# 12_OUT.net
KiCad netlist of a schematic drawn in Altium Designer
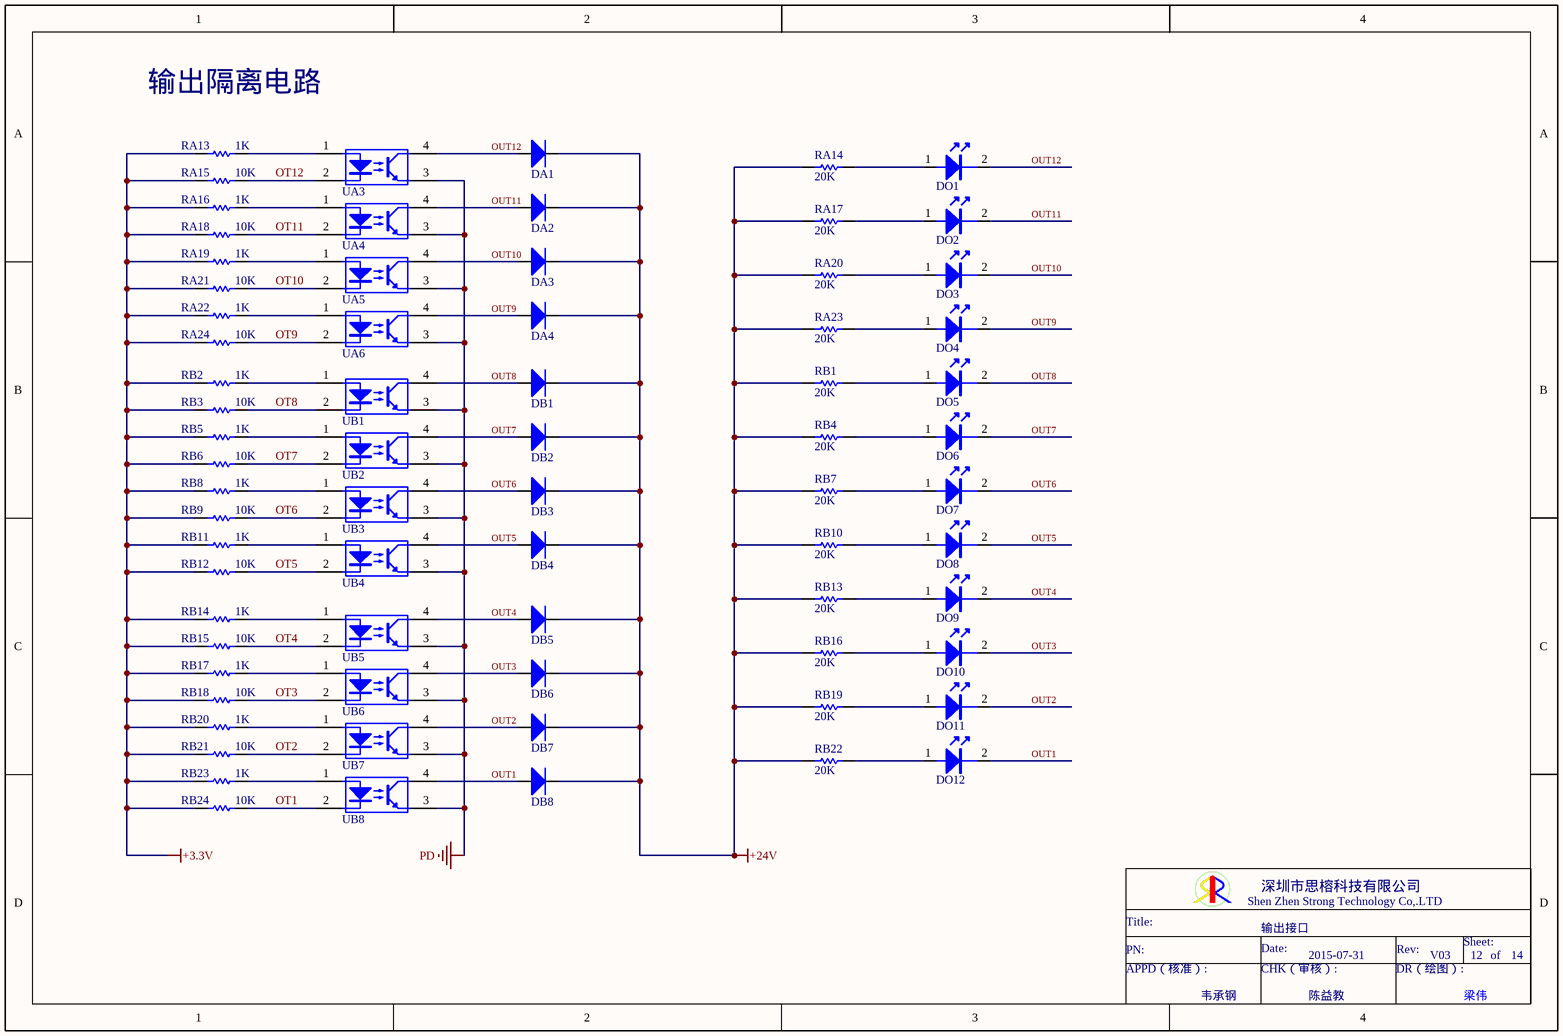
[diagram p0: 12_OUT.SchDoc]

(export (version "E")
  (design (tool "Eeschema 10.0.6"))
  (components
    (comp (ref "DA1")
      (value "IN4148W T4")
      (footprint "1206D")
      (description "二极管")
      (libsource (lib "Mylibrary") (part "D"))
    )
    (comp (ref "DA2")
      (value "IN4148W T4")
      (footprint "1206D")
      (description "二极管")
      (libsource (lib "Mylibrary") (part "D"))
    )
    (comp (ref "DA3")
      (value "IN4148W T4")
      (footprint "1206D")
      (description "二极管")
      (libsource (lib "Mylibrary") (part "D"))
    )
    (comp (ref "DA4")
      (value "IN4148W T4")
      (footprint "1206D")
      (description "二极管")
      (libsource (lib "Mylibrary") (part "D"))
    )
    (comp (ref "DB1")
      (value "IN4148W T4")
      (footprint "1206D")
      (description "二极管")
      (libsource (lib "Mylibrary") (part "D"))
    )
    (comp (ref "DB2")
      (value "IN4148W T4")
      (footprint "1206D")
      (description "二极管")
      (libsource (lib "Mylibrary") (part "D"))
    )
    (comp (ref "DB3")
      (value "IN4148W T4")
      (footprint "1206D")
      (description "二极管")
      (libsource (lib "Mylibrary") (part "D"))
    )
    (comp (ref "DB4")
      (value "IN4148W T4")
      (footprint "1206D")
      (description "二极管")
      (libsource (lib "Mylibrary") (part "D"))
    )
    (comp (ref "DB5")
      (value "IN4148W T4")
      (footprint "1206D")
      (description "二极管")
      (libsource (lib "Mylibrary") (part "D"))
    )
    (comp (ref "DB6")
      (value "IN4148W T4")
      (footprint "1206D")
      (description "二极管")
      (libsource (lib "Mylibrary") (part "D"))
    )
    (comp (ref "DB7")
      (value "IN4148W T4")
      (footprint "1206D")
      (description "二极管")
      (libsource (lib "Mylibrary") (part "D"))
    )
    (comp (ref "DB8")
      (value "IN4148W T4")
      (footprint "1206D")
      (description "二极管")
      (libsource (lib "Mylibrary") (part "D"))
    )
    (comp (ref "DO1")
      (value "LED灯 白发红光")
      (footprint "D0603")
      (description "LED灯")
      (libsource (lib "Mylibrary") (part "LED"))
    )
    (comp (ref "DO2")
      (value "LED灯 白发红光")
      (footprint "D0603")
      (description "LED灯")
      (libsource (lib "Mylibrary") (part "LED"))
    )
    (comp (ref "DO3")
      (value "LED灯 白发红光")
      (footprint "D0603")
      (description "LED灯")
      (libsource (lib "Mylibrary") (part "LED"))
    )
    (comp (ref "DO4")
      (value "LED灯 白发红光")
      (footprint "D0603")
      (description "LED灯")
      (libsource (lib "Mylibrary") (part "LED"))
    )
    (comp (ref "DO5")
      (value "LED灯 白发红光")
      (footprint "D0603")
      (description "LED灯")
      (libsource (lib "Mylibrary") (part "LED"))
    )
    (comp (ref "DO6")
      (value "LED灯 白发红光")
      (footprint "D0603")
      (description "LED灯")
      (libsource (lib "Mylibrary") (part "LED"))
    )
    (comp (ref "DO7")
      (value "LED灯 白发红光")
      (footprint "D0603")
      (description "LED灯")
      (libsource (lib "Mylibrary") (part "LED"))
    )
    (comp (ref "DO8")
      (value "LED灯 白发红光")
      (footprint "D0603")
      (description "LED灯")
      (libsource (lib "Mylibrary") (part "LED"))
    )
    (comp (ref "DO9")
      (value "LED灯 白发红光")
      (footprint "D0603")
      (description "LED灯")
      (libsource (lib "Mylibrary") (part "LED"))
    )
    (comp (ref "DO10")
      (value "LED灯 白发红光")
      (footprint "D0603")
      (description "LED灯")
      (libsource (lib "Mylibrary") (part "LED"))
    )
    (comp (ref "DO11")
      (value "LED灯 白发红光")
      (footprint "D0603")
      (description "LED灯")
      (libsource (lib "Mylibrary") (part "LED"))
    )
    (comp (ref "DO12")
      (value "LED灯 白发红光")
      (footprint "D0603")
      (description "LED灯")
      (libsource (lib "Mylibrary") (part "LED"))
    )
    (comp (ref "RA13") (value "1K") (footprint "0603R") (libsource (lib "Mylibrary") (part "RES")))
    (comp (ref "RA14") (value "20K") (footprint "0603R") (libsource (lib "Mylibrary") (part "RES")))
    (comp (ref "RA15") (value "10K") (footprint "0603R") (libsource (lib "Mylibrary") (part "RES")))
    (comp (ref "RA16") (value "1K") (footprint "0603R") (libsource (lib "Mylibrary") (part "RES")))
    (comp (ref "RA17") (value "20K") (footprint "0603R") (libsource (lib "Mylibrary") (part "RES")))
    (comp (ref "RA18") (value "10K") (footprint "0603R") (libsource (lib "Mylibrary") (part "RES")))
    (comp (ref "RA19") (value "1K") (footprint "0603R") (libsource (lib "Mylibrary") (part "RES")))
    (comp (ref "RA20") (value "20K") (footprint "0603R") (libsource (lib "Mylibrary") (part "RES")))
    (comp (ref "RA21") (value "10K") (footprint "0603R") (libsource (lib "Mylibrary") (part "RES")))
    (comp (ref "RA22") (value "1K") (footprint "0603R") (libsource (lib "Mylibrary") (part "RES")))
    (comp (ref "RA23") (value "20K") (footprint "0603R") (libsource (lib "Mylibrary") (part "RES")))
    (comp (ref "RA24") (value "10K") (footprint "0603R") (libsource (lib "Mylibrary") (part "RES")))
    (comp (ref "RB1") (value "20K") (footprint "0603R") (libsource (lib "Mylibrary") (part "RES")))
    (comp (ref "RB2") (value "1K") (footprint "0603R") (libsource (lib "Mylibrary") (part "RES")))
    (comp (ref "RB3") (value "10K") (footprint "0603R") (libsource (lib "Mylibrary") (part "RES")))
    (comp (ref "RB4") (value "20K") (footprint "0603R") (libsource (lib "Mylibrary") (part "RES")))
    (comp (ref "RB5") (value "1K") (footprint "0603R") (libsource (lib "Mylibrary") (part "RES")))
    (comp (ref "RB6") (value "10K") (footprint "0603R") (libsource (lib "Mylibrary") (part "RES")))
    (comp (ref "RB7") (value "20K") (footprint "0603R") (libsource (lib "Mylibrary") (part "RES")))
    (comp (ref "RB8") (value "1K") (footprint "0603R") (libsource (lib "Mylibrary") (part "RES")))
    (comp (ref "RB9") (value "10K") (footprint "0603R") (libsource (lib "Mylibrary") (part "RES")))
    (comp (ref "RB10") (value "20K") (footprint "0603R") (libsource (lib "Mylibrary") (part "RES")))
    (comp (ref "RB11") (value "1K") (footprint "0603R") (libsource (lib "Mylibrary") (part "RES")))
    (comp (ref "RB12") (value "10K") (footprint "0603R") (libsource (lib "Mylibrary") (part "RES")))
    (comp (ref "RB13") (value "20K") (footprint "0603R") (libsource (lib "Mylibrary") (part "RES")))
    (comp (ref "RB14") (value "1K") (footprint "0603R") (libsource (lib "Mylibrary") (part "RES")))
    (comp (ref "RB15") (value "10K") (footprint "0603R") (libsource (lib "Mylibrary") (part "RES")))
    (comp (ref "RB16") (value "20K") (footprint "0603R") (libsource (lib "Mylibrary") (part "RES")))
    (comp (ref "RB17") (value "1K") (footprint "0603R") (libsource (lib "Mylibrary") (part "RES")))
    (comp (ref "RB18") (value "10K") (footprint "0603R") (libsource (lib "Mylibrary") (part "RES")))
    (comp (ref "RB19") (value "20K") (footprint "0603R") (libsource (lib "Mylibrary") (part "RES")))
    (comp (ref "RB20") (value "1K") (footprint "0603R") (libsource (lib "Mylibrary") (part "RES")))
    (comp (ref "RB21") (value "10K") (footprint "0603R") (libsource (lib "Mylibrary") (part "RES")))
    (comp (ref "RB22") (value "20K") (footprint "0603R") (libsource (lib "Mylibrary") (part "RES")))
    (comp (ref "RB23") (value "1K") (footprint "0603R") (libsource (lib "Mylibrary") (part "RES")))
    (comp (ref "RB24") (value "10K") (footprint "0603R") (libsource (lib "Mylibrary") (part "RES")))
    (comp (ref "UA3")
      (value "AQY212GS")
      (footprint "SOP4-2.54")
      (libsource (lib "Mylibrary") (part "TLP281"))
    )
    (comp (ref "UA4")
      (value "AQY212GS")
      (footprint "SOP4-2.54")
      (libsource (lib "Mylibrary") (part "TLP281"))
    )
    (comp (ref "UA5")
      (value "AQY212GS")
      (footprint "SOP4-2.54")
      (libsource (lib "Mylibrary") (part "TLP281"))
    )
    (comp (ref "UA6")
      (value "AQY212GS")
      (footprint "SOP4-2.54")
      (libsource (lib "Mylibrary") (part "TLP281"))
    )
    (comp (ref "UB1")
      (value "AQY212GS")
      (footprint "SOP4-2.54")
      (libsource (lib "Mylibrary") (part "TLP281"))
    )
    (comp (ref "UB2")
      (value "AQY212GS")
      (footprint "SOP4-2.54")
      (libsource (lib "Mylibrary") (part "TLP281"))
    )
    (comp (ref "UB3")
      (value "AQY212GS")
      (footprint "SOP4-2.54")
      (libsource (lib "Mylibrary") (part "TLP281"))
    )
    (comp (ref "UB4")
      (value "AQY212GS")
      (footprint "SOP4-2.54")
      (libsource (lib "Mylibrary") (part "TLP281"))
    )
    (comp (ref "UB5")
      (value "AQY212GS")
      (footprint "SOP4-2.54")
      (libsource (lib "Mylibrary") (part "TLP281"))
    )
    (comp (ref "UB6")
      (value "AQY212GS")
      (footprint "SOP4-2.54")
      (libsource (lib "Mylibrary") (part "TLP281"))
    )
    (comp (ref "UB7")
      (value "AQY212GS")
      (footprint "SOP4-2.54")
      (libsource (lib "Mylibrary") (part "TLP281"))
    )
    (comp (ref "UB8")
      (value "AQY212GS")
      (footprint "SOP4-2.54")
      (libsource (lib "Mylibrary") (part "TLP281"))
    )
  )
  (nets
    (net (code "1") (name "+3.3V") (class "Default")
      (node (ref "RA13") (pin "1") (pinfunction "1_1") (pintype "passive"))
      (node (ref "RA15") (pin "1") (pinfunction "1_1") (pintype "passive"))
      (node (ref "RA16") (pin "1") (pinfunction "1_1") (pintype "passive"))
      (node (ref "RA18") (pin "1") (pinfunction "1_1") (pintype "passive"))
      (node (ref "RA19") (pin "1") (pinfunction "1_1") (pintype "passive"))
      (node (ref "RA21") (pin "1") (pinfunction "1_1") (pintype "passive"))
      (node (ref "RA22") (pin "1") (pinfunction "1_1") (pintype "passive"))
      (node (ref "RA24") (pin "1") (pinfunction "1_1") (pintype "passive"))
      (node (ref "RB11") (pin "1") (pinfunction "1_1") (pintype "passive"))
      (node (ref "RB12") (pin "1") (pinfunction "1_1") (pintype "passive"))
      (node (ref "RB14") (pin "1") (pinfunction "1_1") (pintype "passive"))
      (node (ref "RB15") (pin "1") (pinfunction "1_1") (pintype "passive"))
      (node (ref "RB17") (pin "1") (pinfunction "1_1") (pintype "passive"))
      (node (ref "RB18") (pin "1") (pinfunction "1_1") (pintype "passive"))
      (node (ref "RB2") (pin "1") (pinfunction "1_1") (pintype "passive"))
      (node (ref "RB20") (pin "1") (pinfunction "1_1") (pintype "passive"))
      (node (ref "RB21") (pin "1") (pinfunction "1_1") (pintype "passive"))
      (node (ref "RB23") (pin "1") (pinfunction "1_1") (pintype "passive"))
      (node (ref "RB24") (pin "1") (pinfunction "1_1") (pintype "passive"))
      (node (ref "RB3") (pin "1") (pinfunction "1_1") (pintype "passive"))
      (node (ref "RB5") (pin "1") (pinfunction "1_1") (pintype "passive"))
      (node (ref "RB6") (pin "1") (pinfunction "1_1") (pintype "passive"))
      (node (ref "RB8") (pin "1") (pinfunction "1_1") (pintype "passive"))
      (node (ref "RB9") (pin "1") (pinfunction "1_1") (pintype "passive"))
    )
    (net (code "2") (name "+24V") (class "Default")
      (node (ref "DA1") (pin "2") (pinfunction "2_2") (pintype "passive"))
      (node (ref "DA2") (pin "2") (pinfunction "2_2") (pintype "passive"))
      (node (ref "DA3") (pin "2") (pinfunction "2_2") (pintype "passive"))
      (node (ref "DA4") (pin "2") (pinfunction "2_2") (pintype "passive"))
      (node (ref "DB1") (pin "2") (pinfunction "2_2") (pintype "passive"))
      (node (ref "DB2") (pin "2") (pinfunction "2_2") (pintype "passive"))
      (node (ref "DB3") (pin "2") (pinfunction "2_2") (pintype "passive"))
      (node (ref "DB4") (pin "2") (pinfunction "2_2") (pintype "passive"))
      (node (ref "DB5") (pin "2") (pinfunction "2_2") (pintype "passive"))
      (node (ref "DB6") (pin "2") (pinfunction "2_2") (pintype "passive"))
      (node (ref "DB7") (pin "2") (pinfunction "2_2") (pintype "passive"))
      (node (ref "DB8") (pin "2") (pinfunction "2_2") (pintype "passive"))
      (node (ref "RA14") (pin "1") (pinfunction "1_1") (pintype "passive"))
      (node (ref "RA17") (pin "1") (pinfunction "1_1") (pintype "passive"))
      (node (ref "RA20") (pin "1") (pinfunction "1_1") (pintype "passive"))
      (node (ref "RA23") (pin "1") (pinfunction "1_1") (pintype "passive"))
      (node (ref "RB1") (pin "1") (pinfunction "1_1") (pintype "passive"))
      (node (ref "RB10") (pin "1") (pinfunction "1_1") (pintype "passive"))
      (node (ref "RB13") (pin "1") (pinfunction "1_1") (pintype "passive"))
      (node (ref "RB16") (pin "1") (pinfunction "1_1") (pintype "passive"))
      (node (ref "RB19") (pin "1") (pinfunction "1_1") (pintype "passive"))
      (node (ref "RB22") (pin "1") (pinfunction "1_1") (pintype "passive"))
      (node (ref "RB4") (pin "1") (pinfunction "1_1") (pintype "passive"))
      (node (ref "RB7") (pin "1") (pinfunction "1_1") (pintype "passive"))
    )
    (net (code "3") (name "/OT1") (class "Default")
      (node (ref "RB24") (pin "2") (pinfunction "2_2") (pintype "passive"))
      (node (ref "UB8") (pin "2") (pinfunction "LED_Cathode_2") (pintype "passive"))
    )
    (net (code "4") (name "/OT2") (class "Default")
      (node (ref "RB21") (pin "2") (pinfunction "2_2") (pintype "passive"))
      (node (ref "UB7") (pin "2") (pinfunction "LED_Cathode_2") (pintype "passive"))
    )
    (net (code "5") (name "/OT3") (class "Default")
      (node (ref "RB18") (pin "2") (pinfunction "2_2") (pintype "passive"))
      (node (ref "UB6") (pin "2") (pinfunction "LED_Cathode_2") (pintype "passive"))
    )
    (net (code "6") (name "/OT4") (class "Default")
      (node (ref "RB15") (pin "2") (pinfunction "2_2") (pintype "passive"))
      (node (ref "UB5") (pin "2") (pinfunction "LED_Cathode_2") (pintype "passive"))
    )
    (net (code "7") (name "/OT5") (class "Default")
      (node (ref "RB12") (pin "2") (pinfunction "2_2") (pintype "passive"))
      (node (ref "UB4") (pin "2") (pinfunction "LED_Cathode_2") (pintype "passive"))
    )
    (net (code "8") (name "/OT6") (class "Default")
      (node (ref "RB9") (pin "2") (pinfunction "2_2") (pintype "passive"))
      (node (ref "UB3") (pin "2") (pinfunction "LED_Cathode_2") (pintype "passive"))
    )
    (net (code "9") (name "/OT7") (class "Default")
      (node (ref "RB6") (pin "2") (pinfunction "2_2") (pintype "passive"))
      (node (ref "UB2") (pin "2") (pinfunction "LED_Cathode_2") (pintype "passive"))
    )
    (net (code "10") (name "/OT8") (class "Default")
      (node (ref "RB3") (pin "2") (pinfunction "2_2") (pintype "passive"))
      (node (ref "UB1") (pin "2") (pinfunction "LED_Cathode_2") (pintype "passive"))
    )
    (net (code "11") (name "/OT9") (class "Default")
      (node (ref "RA24") (pin "2") (pinfunction "2_2") (pintype "passive"))
      (node (ref "UA6") (pin "2") (pinfunction "LED_Cathode_2") (pintype "passive"))
    )
    (net (code "12") (name "/OT10") (class "Default")
      (node (ref "RA21") (pin "2") (pinfunction "2_2") (pintype "passive"))
      (node (ref "UA5") (pin "2") (pinfunction "LED_Cathode_2") (pintype "passive"))
    )
    (net (code "13") (name "/OT11") (class "Default")
      (node (ref "RA18") (pin "2") (pinfunction "2_2") (pintype "passive"))
      (node (ref "UA4") (pin "2") (pinfunction "LED_Cathode_2") (pintype "passive"))
    )
    (net (code "14") (name "/OT12") (class "Default")
      (node (ref "RA15") (pin "2") (pinfunction "2_2") (pintype "passive"))
      (node (ref "UA3") (pin "2") (pinfunction "LED_Cathode_2") (pintype "passive"))
    )
    (net (code "15") (name "/OUT1") (class "Default")
      (node (ref "DB8") (pin "1") (pinfunction "1_1") (pintype "passive"))
      (node (ref "DO12") (pin "2") (pinfunction "2_2") (pintype "passive"))
      (node (ref "UB8") (pin "4") (pinfunction "Collector_4") (pintype "passive"))
    )
    (net (code "16") (name "/OUT2") (class "Default")
      (node (ref "DB7") (pin "1") (pinfunction "1_1") (pintype "passive"))
      (node (ref "DO11") (pin "2") (pinfunction "2_2") (pintype "passive"))
      (node (ref "UB7") (pin "4") (pinfunction "Collector_4") (pintype "passive"))
    )
    (net (code "17") (name "/OUT3") (class "Default")
      (node (ref "DB6") (pin "1") (pinfunction "1_1") (pintype "passive"))
      (node (ref "DO10") (pin "2") (pinfunction "2_2") (pintype "passive"))
      (node (ref "UB6") (pin "4") (pinfunction "Collector_4") (pintype "passive"))
    )
    (net (code "18") (name "/OUT4") (class "Default")
      (node (ref "DB5") (pin "1") (pinfunction "1_1") (pintype "passive"))
      (node (ref "DO9") (pin "2") (pinfunction "2_2") (pintype "passive"))
      (node (ref "UB5") (pin "4") (pinfunction "Collector_4") (pintype "passive"))
    )
    (net (code "19") (name "/OUT5") (class "Default")
      (node (ref "DB4") (pin "1") (pinfunction "1_1") (pintype "passive"))
      (node (ref "DO8") (pin "2") (pinfunction "2_2") (pintype "passive"))
      (node (ref "UB4") (pin "4") (pinfunction "Collector_4") (pintype "passive"))
    )
    (net (code "20") (name "/OUT6") (class "Default")
      (node (ref "DB3") (pin "1") (pinfunction "1_1") (pintype "passive"))
      (node (ref "DO7") (pin "2") (pinfunction "2_2") (pintype "passive"))
      (node (ref "UB3") (pin "4") (pinfunction "Collector_4") (pintype "passive"))
    )
    (net (code "21") (name "/OUT7") (class "Default")
      (node (ref "DB2") (pin "1") (pinfunction "1_1") (pintype "passive"))
      (node (ref "DO6") (pin "2") (pinfunction "2_2") (pintype "passive"))
      (node (ref "UB2") (pin "4") (pinfunction "Collector_4") (pintype "passive"))
    )
    (net (code "22") (name "/OUT8") (class "Default")
      (node (ref "DB1") (pin "1") (pinfunction "1_1") (pintype "passive"))
      (node (ref "DO5") (pin "2") (pinfunction "2_2") (pintype "passive"))
      (node (ref "UB1") (pin "4") (pinfunction "Collector_4") (pintype "passive"))
    )
    (net (code "23") (name "/OUT9") (class "Default")
      (node (ref "DA4") (pin "1") (pinfunction "1_1") (pintype "passive"))
      (node (ref "DO4") (pin "2") (pinfunction "2_2") (pintype "passive"))
      (node (ref "UA6") (pin "4") (pinfunction "Collector_4") (pintype "passive"))
    )
    (net (code "24") (name "/OUT10") (class "Default")
      (node (ref "DA3") (pin "1") (pinfunction "1_1") (pintype "passive"))
      (node (ref "DO3") (pin "2") (pinfunction "2_2") (pintype "passive"))
      (node (ref "UA5") (pin "4") (pinfunction "Collector_4") (pintype "passive"))
    )
    (net (code "25") (name "/OUT11") (class "Default")
      (node (ref "DA2") (pin "1") (pinfunction "1_1") (pintype "passive"))
      (node (ref "DO2") (pin "2") (pinfunction "2_2") (pintype "passive"))
      (node (ref "UA4") (pin "4") (pinfunction "Collector_4") (pintype "passive"))
    )
    (net (code "26") (name "/OUT12") (class "Default")
      (node (ref "DA1") (pin "1") (pinfunction "1_1") (pintype "passive"))
      (node (ref "DO1") (pin "2") (pinfunction "2_2") (pintype "passive"))
      (node (ref "UA3") (pin "4") (pinfunction "Collector_4") (pintype "passive"))
    )
    (net (code "27") (name "Net-(DO1-Pad1)") (class "Default")
      (node (ref "DO1") (pin "1") (pinfunction "1_1") (pintype "passive"))
      (node (ref "RA14") (pin "2") (pinfunction "2_2") (pintype "passive"))
    )
    (net (code "28") (name "Net-(DO2-Pad1)") (class "Default")
      (node (ref "DO2") (pin "1") (pinfunction "1_1") (pintype "passive"))
      (node (ref "RA17") (pin "2") (pinfunction "2_2") (pintype "passive"))
    )
    (net (code "29") (name "Net-(DO3-Pad1)") (class "Default")
      (node (ref "DO3") (pin "1") (pinfunction "1_1") (pintype "passive"))
      (node (ref "RA20") (pin "2") (pinfunction "2_2") (pintype "passive"))
    )
    (net (code "30") (name "Net-(DO4-Pad1)") (class "Default")
      (node (ref "DO4") (pin "1") (pinfunction "1_1") (pintype "passive"))
      (node (ref "RA23") (pin "2") (pinfunction "2_2") (pintype "passive"))
    )
    (net (code "31") (name "Net-(DO5-Pad1)") (class "Default")
      (node (ref "DO5") (pin "1") (pinfunction "1_1") (pintype "passive"))
      (node (ref "RB1") (pin "2") (pinfunction "2_2") (pintype "passive"))
    )
    (net (code "32") (name "Net-(DO6-Pad1)") (class "Default")
      (node (ref "DO6") (pin "1") (pinfunction "1_1") (pintype "passive"))
      (node (ref "RB4") (pin "2") (pinfunction "2_2") (pintype "passive"))
    )
    (net (code "33") (name "Net-(DO7-Pad1)") (class "Default")
      (node (ref "DO7") (pin "1") (pinfunction "1_1") (pintype "passive"))
      (node (ref "RB7") (pin "2") (pinfunction "2_2") (pintype "passive"))
    )
    (net (code "34") (name "Net-(DO8-Pad1)") (class "Default")
      (node (ref "DO8") (pin "1") (pinfunction "1_1") (pintype "passive"))
      (node (ref "RB10") (pin "2") (pinfunction "2_2") (pintype "passive"))
    )
    (net (code "35") (name "Net-(DO9-Pad1)") (class "Default")
      (node (ref "DO9") (pin "1") (pinfunction "1_1") (pintype "passive"))
      (node (ref "RB13") (pin "2") (pinfunction "2_2") (pintype "passive"))
    )
    (net (code "36") (name "Net-(DO10-Pad1)") (class "Default")
      (node (ref "DO10") (pin "1") (pinfunction "1_1") (pintype "passive"))
      (node (ref "RB16") (pin "2") (pinfunction "2_2") (pintype "passive"))
    )
    (net (code "37") (name "Net-(DO11-Pad1)") (class "Default")
      (node (ref "DO11") (pin "1") (pinfunction "1_1") (pintype "passive"))
      (node (ref "RB19") (pin "2") (pinfunction "2_2") (pintype "passive"))
    )
    (net (code "38") (name "Net-(DO12-Pad1)") (class "Default")
      (node (ref "DO12") (pin "1") (pinfunction "1_1") (pintype "passive"))
      (node (ref "RB22") (pin "2") (pinfunction "2_2") (pintype "passive"))
    )
    (net (code "39") (name "Net-(UA3-LED_Anode)") (class "Default")
      (node (ref "RA13") (pin "2") (pinfunction "2_2") (pintype "passive"))
      (node (ref "UA3") (pin "1") (pinfunction "LED_Anode_1") (pintype "passive"))
    )
    (net (code "40") (name "Net-(UA4-LED_Anode)") (class "Default")
      (node (ref "RA16") (pin "2") (pinfunction "2_2") (pintype "passive"))
      (node (ref "UA4") (pin "1") (pinfunction "LED_Anode_1") (pintype "passive"))
    )
    (net (code "41") (name "Net-(UA5-LED_Anode)") (class "Default")
      (node (ref "RA19") (pin "2") (pinfunction "2_2") (pintype "passive"))
      (node (ref "UA5") (pin "1") (pinfunction "LED_Anode_1") (pintype "passive"))
    )
    (net (code "42") (name "Net-(UA6-LED_Anode)") (class "Default")
      (node (ref "RA22") (pin "2") (pinfunction "2_2") (pintype "passive"))
      (node (ref "UA6") (pin "1") (pinfunction "LED_Anode_1") (pintype "passive"))
    )
    (net (code "43") (name "Net-(UB1-LED_Anode)") (class "Default")
      (node (ref "RB2") (pin "2") (pinfunction "2_2") (pintype "passive"))
      (node (ref "UB1") (pin "1") (pinfunction "LED_Anode_1") (pintype "passive"))
    )
    (net (code "44") (name "Net-(UB2-LED_Anode)") (class "Default")
      (node (ref "RB5") (pin "2") (pinfunction "2_2") (pintype "passive"))
      (node (ref "UB2") (pin "1") (pinfunction "LED_Anode_1") (pintype "passive"))
    )
    (net (code "45") (name "Net-(UB3-LED_Anode)") (class "Default")
      (node (ref "RB8") (pin "2") (pinfunction "2_2") (pintype "passive"))
      (node (ref "UB3") (pin "1") (pinfunction "LED_Anode_1") (pintype "passive"))
    )
    (net (code "46") (name "Net-(UB4-LED_Anode)") (class "Default")
      (node (ref "RB11") (pin "2") (pinfunction "2_2") (pintype "passive"))
      (node (ref "UB4") (pin "1") (pinfunction "LED_Anode_1") (pintype "passive"))
    )
    (net (code "47") (name "Net-(UB5-LED_Anode)") (class "Default")
      (node (ref "RB14") (pin "2") (pinfunction "2_2") (pintype "passive"))
      (node (ref "UB5") (pin "1") (pinfunction "LED_Anode_1") (pintype "passive"))
    )
    (net (code "48") (name "Net-(UB6-LED_Anode)") (class "Default")
      (node (ref "RB17") (pin "2") (pinfunction "2_2") (pintype "passive"))
      (node (ref "UB6") (pin "1") (pinfunction "LED_Anode_1") (pintype "passive"))
    )
    (net (code "49") (name "Net-(UB7-LED_Anode)") (class "Default")
      (node (ref "RB20") (pin "2") (pinfunction "2_2") (pintype "passive"))
      (node (ref "UB7") (pin "1") (pinfunction "LED_Anode_1") (pintype "passive"))
    )
    (net (code "50") (name "Net-(UB8-LED_Anode)") (class "Default")
      (node (ref "RB23") (pin "2") (pinfunction "2_2") (pintype "passive"))
      (node (ref "UB8") (pin "1") (pinfunction "LED_Anode_1") (pintype "passive"))
    )
    (net (code "51") (name "PD") (class "Default")
      (node (ref "UA3") (pin "3") (pinfunction "Emitter_3") (pintype "passive"))
      (node (ref "UA4") (pin "3") (pinfunction "Emitter_3") (pintype "passive"))
      (node (ref "UA5") (pin "3") (pinfunction "Emitter_3") (pintype "passive"))
      (node (ref "UA6") (pin "3") (pinfunction "Emitter_3") (pintype "passive"))
      (node (ref "UB1") (pin "3") (pinfunction "Emitter_3") (pintype "passive"))
      (node (ref "UB2") (pin "3") (pinfunction "Emitter_3") (pintype "passive"))
      (node (ref "UB3") (pin "3") (pinfunction "Emitter_3") (pintype "passive"))
      (node (ref "UB4") (pin "3") (pinfunction "Emitter_3") (pintype "passive"))
      (node (ref "UB5") (pin "3") (pinfunction "Emitter_3") (pintype "passive"))
      (node (ref "UB6") (pin "3") (pinfunction "Emitter_3") (pintype "passive"))
      (node (ref "UB7") (pin "3") (pinfunction "Emitter_3") (pintype "passive"))
      (node (ref "UB8") (pin "3") (pinfunction "Emitter_3") (pintype "passive"))
    )
  )
)
